# LilyPad-E-Sewing-Kit.net
KiCad netlist of a schematic drawn in EAGLE
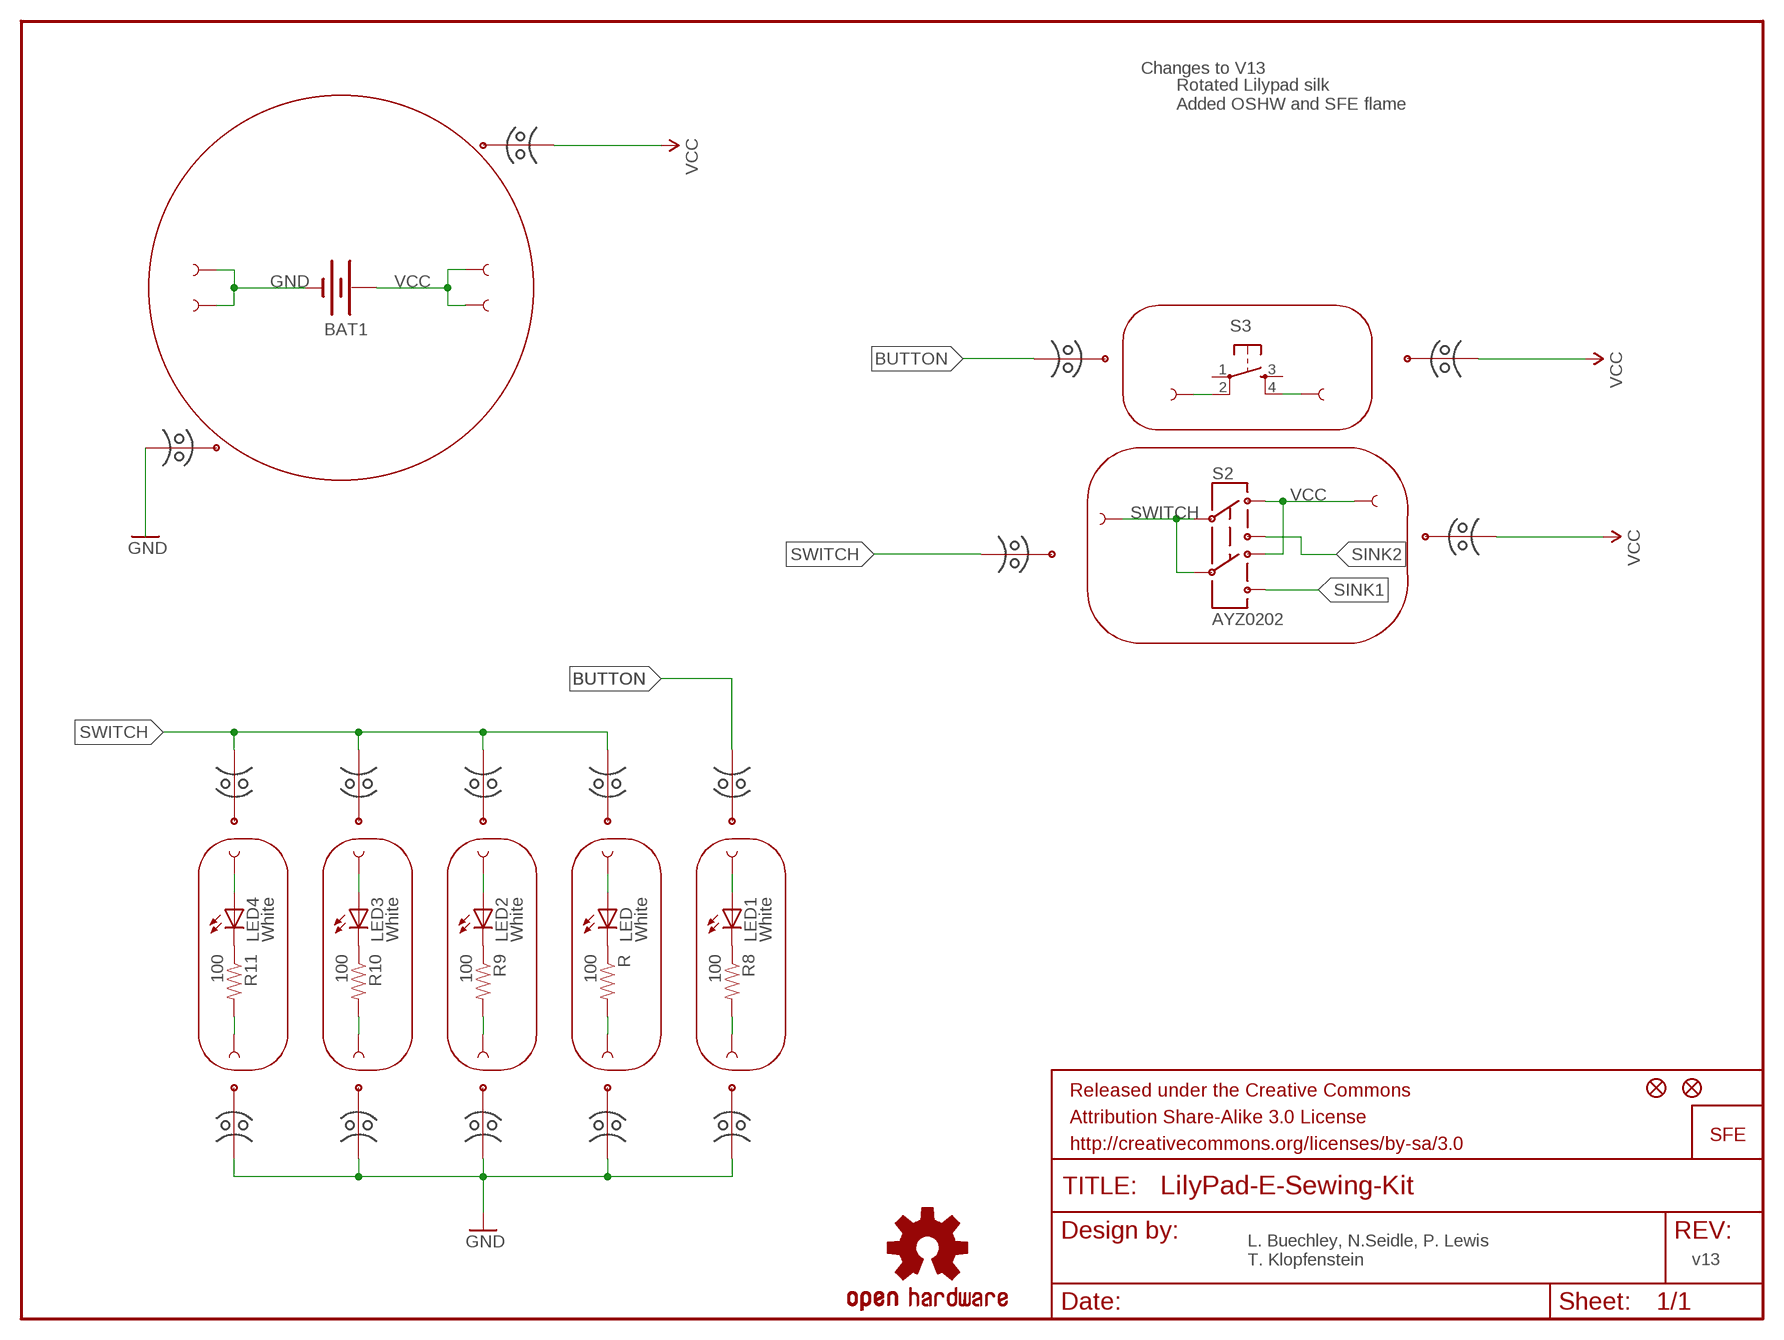
[diagram p0: schematic, sheet 1]

(export (version "E")
  (design (tool "Eeschema 10.0.6"))
  (components
    (comp (ref "BAT1")
      (value "BATTERYBATTCON_20MM_4LEGS")
      (footprint "eagle-import:BATTCON_20MM_4LEGS")
      (libsource (lib "eagle-import") (part "BATTERYBATTCON_20MM_4LEGS"))
    )
    (comp (ref "BUTTON-")
      (value "SEWTAP8")
      (footprint "eagle-import:PETAL-SMALL")
      (libsource (lib "eagle-import") (part "SEWTAP4"))
    )
    (comp (ref "BUTTONS")
      (value "SEWTAP8")
      (footprint "eagle-import:PETAL-SMALL")
      (libsource (lib "eagle-import") (part "SEWTAP4"))
    )
    (comp (ref "JP1")
      (value "FIDUCIAL1X2")
      (footprint "eagle-import:FIDUCIAL-1X2")
      (libsource (lib "eagle-import") (part "FIDUCIAL1X2"))
    )
    (comp (ref "JP2")
      (value "LOGO-SFESK")
      (footprint "eagle-import:SFE-LOGO-FLAME")
      (libsource (lib "eagle-import") (part "LOGO-SFESK"))
    )
    (comp (ref "JP4")
      (value "FIDUCIAL1X2")
      (footprint "eagle-import:FIDUCIAL-1X2")
      (libsource (lib "eagle-import") (part "FIDUCIAL1X2"))
    )
    (comp (ref "LED")
      (value "White")
      (footprint "eagle-import:LED-1206")
      (libsource (lib "eagle-import") (part "LED1206"))
    )
    (comp (ref "LED+")
      (value "SEWTAP6")
      (footprint "eagle-import:PETAL-SMALL-2SIDE")
      (libsource (lib "eagle-import") (part "SEWTAP6"))
    )
    (comp (ref "LED+1")
      (value "SEWTAP6")
      (footprint "eagle-import:PETAL-SMALL-2SIDE")
      (libsource (lib "eagle-import") (part "SEWTAP6"))
    )
    (comp (ref "LED+2")
      (value "SEWTAP6")
      (footprint "eagle-import:PETAL-SMALL-2SIDE")
      (libsource (lib "eagle-import") (part "SEWTAP6"))
    )
    (comp (ref "LED+3")
      (value "SEWTAP6")
      (footprint "eagle-import:PETAL-SMALL-2SIDE")
      (libsource (lib "eagle-import") (part "SEWTAP6"))
    )
    (comp (ref "LED+4")
      (value "SEWTAP6")
      (footprint "eagle-import:PETAL-SMALL-2SIDE")
      (libsource (lib "eagle-import") (part "SEWTAP6"))
    )
    (comp (ref "LED-")
      (value "SEWTAP6")
      (footprint "eagle-import:PETAL-SMALL-2SIDE")
      (libsource (lib "eagle-import") (part "SEWTAP6"))
    )
    (comp (ref "LED-1")
      (value "SEWTAP6")
      (footprint "eagle-import:PETAL-SMALL-2SIDE")
      (libsource (lib "eagle-import") (part "SEWTAP6"))
    )
    (comp (ref "LED-2")
      (value "SEWTAP6")
      (footprint "eagle-import:PETAL-SMALL-2SIDE")
      (libsource (lib "eagle-import") (part "SEWTAP6"))
    )
    (comp (ref "LED-3")
      (value "SEWTAP6")
      (footprint "eagle-import:PETAL-SMALL-2SIDE")
      (libsource (lib "eagle-import") (part "SEWTAP6"))
    )
    (comp (ref "LED-4")
      (value "SEWTAP6")
      (footprint "eagle-import:PETAL-SMALL-2SIDE")
      (libsource (lib "eagle-import") (part "SEWTAP6"))
    )
    (comp (ref "LED1")
      (value "White")
      (footprint "eagle-import:LED-1206")
      (libsource (lib "eagle-import") (part "LED1206"))
    )
    (comp (ref "LED2")
      (value "White")
      (footprint "eagle-import:LED-1206")
      (libsource (lib "eagle-import") (part "LED1206"))
    )
    (comp (ref "LED3")
      (value "White")
      (footprint "eagle-import:LED-1206")
      (libsource (lib "eagle-import") (part "LED1206"))
    )
    (comp (ref "LED4")
      (value "White")
      (footprint "eagle-import:LED-1206")
      (libsource (lib "eagle-import") (part "LED1206"))
    )
    (comp (ref "R")
      (value "100")
      (footprint "eagle-import:0603-RES")
      (libsource (lib "eagle-import") (part "RESISTOR0603-RES"))
    )
    (comp (ref "R8")
      (value "100")
      (footprint "eagle-import:0603-RES")
      (libsource (lib "eagle-import") (part "RESISTOR0603-RES"))
    )
    (comp (ref "R9")
      (value "100")
      (footprint "eagle-import:0603-RES")
      (libsource (lib "eagle-import") (part "RESISTOR0603-RES"))
    )
    (comp (ref "R10")
      (value "100")
      (footprint "eagle-import:0603-RES")
      (libsource (lib "eagle-import") (part "RESISTOR0603-RES"))
    )
    (comp (ref "R11")
      (value "100")
      (footprint "eagle-import:0603-RES")
      (libsource (lib "eagle-import") (part "RESISTOR0603-RES"))
    )
    (comp (ref "S2")
      (value "AYZ0202")
      (footprint "eagle-import:AYZ0202")
      (libsource (lib "eagle-import") (part "AYZ0202"))
    )
    (comp (ref "S3")
      (value "TAC_SWITCHSMD")
      (footprint "eagle-import:TACTILE_SWITCH_SMD")
      (libsource (lib "eagle-import") (part "TAC_SWITCHSMD"))
    )
    (comp (ref "SLIDEOFF")
      (value "SEWTAP8")
      (footprint "eagle-import:PETAL-SMALL")
      (libsource (lib "eagle-import") (part "SEWTAP4"))
    )
    (comp (ref "SLIDEON")
      (value "SEWTAP8")
      (footprint "eagle-import:PETAL-SMALL")
      (libsource (lib "eagle-import") (part "SEWTAP4"))
    )
    (comp (ref "U$1")
      (value "SEWTAP6")
      (footprint "eagle-import:PETAL-SMALL-2SIDE")
      (libsource (lib "eagle-import") (part "SEWTAP6"))
    )
    (comp (ref "U$2")
      (value "SEWTAP6")
      (footprint "eagle-import:PETAL-SMALL-2SIDE")
      (libsource (lib "eagle-import") (part "SEWTAP6"))
    )
    (comp (ref "U$3")
      (value "SEWTAP6")
      (footprint "eagle-import:PETAL-SMALL-2SIDE")
      (libsource (lib "eagle-import") (part "SEWTAP6"))
    )
    (comp (ref "U$4")
      (value "SEWTAP6")
      (footprint "eagle-import:PETAL-SMALL-2SIDE")
      (libsource (lib "eagle-import") (part "SEWTAP6"))
    )
    (comp (ref "U$6")
      (value "MOUSE-BITE-12_HOLES")
      (footprint "eagle-import:MOUST-BITE-1-(2_HOLES)")
      (libsource (lib "eagle-import") (part "MOUSE-BITE-12_HOLES"))
    )
    (comp (ref "U$7")
      (value "MOUSE-BITE-12_HOLES")
      (footprint "eagle-import:MOUST-BITE-1-(2_HOLES)")
      (libsource (lib "eagle-import") (part "MOUSE-BITE-12_HOLES"))
    )
    (comp (ref "U$8")
      (value "OSHW-LOGOS")
      (footprint "eagle-import:OSHW-LOGO-S")
      (libsource (lib "eagle-import") (part "OSHW-LOGOS"))
    )
    (comp (ref "U$10")
      (value "MOUSE-BITE-12_HOLES")
      (footprint "eagle-import:MOUST-BITE-1-(2_HOLES)")
      (libsource (lib "eagle-import") (part "MOUSE-BITE-12_HOLES"))
    )
    (comp (ref "U$11")
      (value "MOUSE-BITE-12_HOLES")
      (footprint "eagle-import:MOUST-BITE-1-(2_HOLES)")
      (libsource (lib "eagle-import") (part "MOUSE-BITE-12_HOLES"))
    )
    (comp (ref "U$12")
      (value "MOUSE-BITE-12_HOLES")
      (footprint "eagle-import:MOUST-BITE-1-(2_HOLES)")
      (libsource (lib "eagle-import") (part "MOUSE-BITE-12_HOLES"))
    )
    (comp (ref "U$13")
      (value "MOUSE-BITE-12_HOLES")
      (footprint "eagle-import:MOUST-BITE-1-(2_HOLES)")
      (libsource (lib "eagle-import") (part "MOUSE-BITE-12_HOLES"))
    )
    (comp (ref "U$14")
      (value "MOUSE-BITE-12_HOLES")
      (footprint "eagle-import:MOUST-BITE-1-(2_HOLES)")
      (libsource (lib "eagle-import") (part "MOUSE-BITE-12_HOLES"))
    )
    (comp (ref "U$15")
      (value "MOUSE-BITE-12_HOLES")
      (footprint "eagle-import:MOUST-BITE-1-(2_HOLES)")
      (libsource (lib "eagle-import") (part "MOUSE-BITE-12_HOLES"))
    )
    (comp (ref "U$16")
      (value "MOUSE-BITE-12_HOLES")
      (footprint "eagle-import:MOUST-BITE-1-(2_HOLES)")
      (libsource (lib "eagle-import") (part "MOUSE-BITE-12_HOLES"))
    )
    (comp (ref "U$17")
      (value "MOUSE-BITE-12_HOLES")
      (footprint "eagle-import:MOUST-BITE-1-(2_HOLES)")
      (libsource (lib "eagle-import") (part "MOUSE-BITE-12_HOLES"))
    )
    (comp (ref "U$18")
      (value "MOUSE-BITE-12_HOLES")
      (footprint "eagle-import:MOUST-BITE-1-(2_HOLES)")
      (libsource (lib "eagle-import") (part "MOUSE-BITE-12_HOLES"))
    )
    (comp (ref "U$19")
      (value "MOUSE-BITE-12_HOLES")
      (footprint "eagle-import:MOUST-BITE-1-(2_HOLES)")
      (libsource (lib "eagle-import") (part "MOUSE-BITE-12_HOLES"))
    )
    (comp (ref "U$40")
      (value "MOUSE-BITE-12_HOLES")
      (footprint "eagle-import:MOUST-BITE-1-(2_HOLES)")
      (libsource (lib "eagle-import") (part "MOUSE-BITE-12_HOLES"))
    )
    (comp (ref "U$42")
      (value "MOUSE-BITE-12_HOLES")
      (footprint "eagle-import:MOUST-BITE-1-(2_HOLES)")
      (libsource (lib "eagle-import") (part "MOUSE-BITE-12_HOLES"))
    )
    (comp (ref "U$44")
      (value "MOUSE-BITE-12_HOLES")
      (footprint "eagle-import:MOUST-BITE-1-(2_HOLES)")
      (libsource (lib "eagle-import") (part "MOUSE-BITE-12_HOLES"))
    )
    (comp (ref "U$46")
      (value "MOUSE-BITE-12_HOLES")
      (footprint "eagle-import:MOUST-BITE-1-(2_HOLES)")
      (libsource (lib "eagle-import") (part "MOUSE-BITE-12_HOLES"))
    )
  )
  (nets
    (net (code "1") (name "BUTTON") (class "Default")
      (node (ref "BUTTONS") (pin "1") (pinfunction "1_1") (pintype "bidirectional"))
      (node (ref "LED+1") (pin "1") (pinfunction "1_1") (pintype "bidirectional"))
      (node (ref "LED1") (pin "A") (pinfunction "A_A") (pintype "passive"))
      (node (ref "S3") (pin "2") (pinfunction "2_2") (pintype "passive"))
      (node (ref "U$13") (pin "P$1") (pinfunction "P$1_P$1") (pintype "bidirectional"))
      (node (ref "U$42") (pin "P$1") (pinfunction "P$1_P$1") (pintype "bidirectional"))
    )
    (net (code "2") (name "GND") (class "Default")
      (node (ref "BAT1") (pin "2") (pinfunction "-_2") (pintype "power_in"))
      (node (ref "LED-") (pin "1") (pinfunction "1_1") (pintype "bidirectional"))
      (node (ref "LED-1") (pin "1") (pinfunction "1_1") (pintype "bidirectional"))
      (node (ref "LED-2") (pin "1") (pinfunction "1_1") (pintype "bidirectional"))
      (node (ref "LED-3") (pin "1") (pinfunction "1_1") (pintype "bidirectional"))
      (node (ref "LED-4") (pin "1") (pinfunction "1_1") (pintype "bidirectional"))
      (node (ref "R") (pin "2") (pinfunction "2_2") (pintype "passive"))
      (node (ref "R10") (pin "2") (pinfunction "2_2") (pintype "passive"))
      (node (ref "R11") (pin "2") (pinfunction "2_2") (pintype "passive"))
      (node (ref "R8") (pin "2") (pinfunction "2_2") (pintype "passive"))
      (node (ref "R9") (pin "2") (pinfunction "2_2") (pintype "passive"))
      (node (ref "U$1") (pin "1") (pinfunction "1_1") (pintype "bidirectional"))
      (node (ref "U$15") (pin "P$1") (pinfunction "P$1_P$1") (pintype "bidirectional"))
      (node (ref "U$16") (pin "P$1") (pinfunction "P$1_P$1") (pintype "bidirectional"))
      (node (ref "U$17") (pin "P$1") (pinfunction "P$1_P$1") (pintype "bidirectional"))
      (node (ref "U$18") (pin "P$1") (pinfunction "P$1_P$1") (pintype "bidirectional"))
      (node (ref "U$19") (pin "P$1") (pinfunction "P$1_P$1") (pintype "bidirectional"))
      (node (ref "U$3") (pin "1") (pinfunction "1_1") (pintype "bidirectional"))
      (node (ref "U$7") (pin "P$1") (pinfunction "P$1_P$1") (pintype "bidirectional"))
    )
    (net (code "3") (name "Net-(LED-PadC)") (class "Default")
      (node (ref "LED") (pin "C") (pinfunction "C_C") (pintype "passive"))
      (node (ref "R") (pin "1") (pinfunction "1_1") (pintype "passive"))
    )
    (net (code "4") (name "Net-(LED1-PadC)") (class "Default")
      (node (ref "LED1") (pin "C") (pinfunction "C_C") (pintype "passive"))
      (node (ref "R8") (pin "1") (pinfunction "1_1") (pintype "passive"))
    )
    (net (code "5") (name "Net-(LED2-PadC)") (class "Default")
      (node (ref "LED2") (pin "C") (pinfunction "C_C") (pintype "passive"))
      (node (ref "R9") (pin "1") (pinfunction "1_1") (pintype "passive"))
    )
    (net (code "6") (name "Net-(LED3-PadC)") (class "Default")
      (node (ref "LED3") (pin "C") (pinfunction "C_C") (pintype "passive"))
      (node (ref "R10") (pin "1") (pinfunction "1_1") (pintype "passive"))
    )
    (net (code "7") (name "Net-(LED4-PadC)") (class "Default")
      (node (ref "LED4") (pin "C") (pinfunction "C_C") (pintype "passive"))
      (node (ref "R11") (pin "1") (pinfunction "1_1") (pintype "passive"))
    )
    (net (code "8") (name "SINK1") (class "Default")
      (node (ref "S2") (pin "4") (pinfunction "6_4") (pintype "bidirectional"))
    )
    (net (code "9") (name "SINK2") (class "Default")
      (node (ref "S2") (pin "1") (pinfunction "3_1") (pintype "bidirectional"))
    )
    (net (code "10") (name "SWITCH") (class "Default")
      (node (ref "LED") (pin "A") (pinfunction "A_A") (pintype "passive"))
      (node (ref "LED+") (pin "1") (pinfunction "1_1") (pintype "bidirectional"))
      (node (ref "LED+2") (pin "1") (pinfunction "1_1") (pintype "bidirectional"))
      (node (ref "LED+3") (pin "1") (pinfunction "1_1") (pintype "bidirectional"))
      (node (ref "LED+4") (pin "1") (pinfunction "1_1") (pintype "bidirectional"))
      (node (ref "LED2") (pin "A") (pinfunction "A_A") (pintype "passive"))
      (node (ref "LED3") (pin "A") (pinfunction "A_A") (pintype "passive"))
      (node (ref "LED4") (pin "A") (pinfunction "A_A") (pintype "passive"))
      (node (ref "S2") (pin "2") (pinfunction "2_2") (pintype "bidirectional"))
      (node (ref "S2") (pin "5") (pinfunction "5_5") (pintype "bidirectional"))
      (node (ref "SLIDEOFF") (pin "1") (pinfunction "1_1") (pintype "bidirectional"))
      (node (ref "U$10") (pin "P$1") (pinfunction "P$1_P$1") (pintype "bidirectional"))
      (node (ref "U$11") (pin "P$1") (pinfunction "P$1_P$1") (pintype "bidirectional"))
      (node (ref "U$12") (pin "P$1") (pinfunction "P$1_P$1") (pintype "bidirectional"))
      (node (ref "U$14") (pin "P$1") (pinfunction "P$1_P$1") (pintype "bidirectional"))
      (node (ref "U$44") (pin "P$1") (pinfunction "P$1_P$1") (pintype "bidirectional"))
    )
    (net (code "11") (name "VCC") (class "Default")
      (node (ref "BAT1") (pin "1") (pinfunction "+_1") (pintype "power_in"))
      (node (ref "BUTTON-") (pin "1") (pinfunction "1_1") (pintype "bidirectional"))
      (node (ref "S2") (pin "3") (pinfunction "1_3") (pintype "bidirectional"))
      (node (ref "S2") (pin "6") (pinfunction "4_6") (pintype "bidirectional"))
      (node (ref "S3") (pin "4") (pinfunction "4_4") (pintype "passive"))
      (node (ref "SLIDEON") (pin "1") (pinfunction "1_1") (pintype "bidirectional"))
      (node (ref "U$2") (pin "1") (pinfunction "1_1") (pintype "bidirectional"))
      (node (ref "U$4") (pin "1") (pinfunction "1_1") (pintype "bidirectional"))
      (node (ref "U$40") (pin "P$1") (pinfunction "P$1_P$1") (pintype "bidirectional"))
      (node (ref "U$46") (pin "P$1") (pinfunction "P$1_P$1") (pintype "bidirectional"))
      (node (ref "U$6") (pin "P$1") (pinfunction "P$1_P$1") (pintype "bidirectional"))
    )
    (net (code "12") (name "unconnected-(S3-Pad1)") (class "Default")
      (node (ref "S3") (pin "1") (pinfunction "1_1") (pintype "passive"))
    )
    (net (code "13") (name "unconnected-(S3-Pad3)") (class "Default")
      (node (ref "S3") (pin "3") (pinfunction "3_3") (pintype "passive"))
    )
  )
)
